# MCU_sheet.net
KiCad netlist of a schematic drawn in Altium Designer
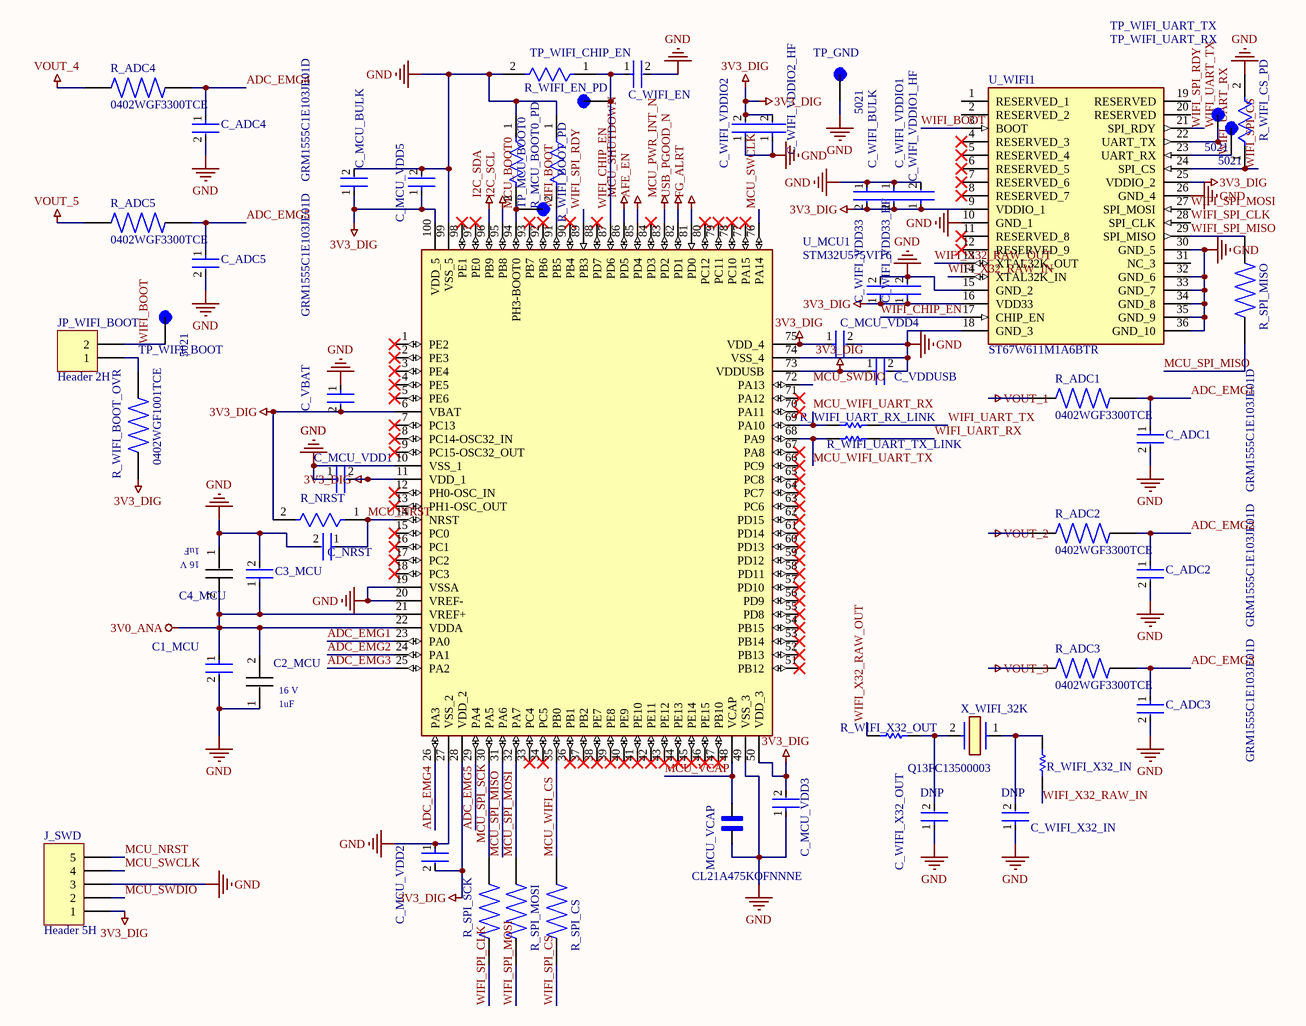
[diagram p0: MCU_sheet.SchDoc]

(export (version "E")
  (design (tool "Eeschema 10.0.6"))
  (components
    (comp (ref "C1_MCU")
      (value "GRM155R61C104KA88D")
      (footprint "96DF66F8-B997-472F-A885-42BCAAE661B2_FP-GRM155-0_05-IPC_C:FP-GRM155-0_05-IPC_C")
      (description "CAP CER 0.1UF 16V X5R 0402")
      (fields (field (name "VOLTAGE") "16V") (field (name "TOLERANCE") "10%"))
      (libsource (lib "EMG_Controlled_R5") (part "EMG_R5_C1_MCU"))
    )
    (comp (ref "C2_MCU")
      (value "MURATA_GRM155C71C105KE11D")
      (footprint "MURATA_GRM155C71C105KE11D_0:*MURATA_GRM155C71C105KE11D_0")
      (description "Murata GRM155C71C105KE11D: 1 uF 16 V X7S +/-10%, 0402/1005 metric")
      (fields (field (name "MF") "Murata") (field (name "MP") "GRM155C71C105KE11D"))
      (libsource (lib "EMG_Controlled_R5") (part "EMG_R5_C2_MCU"))
    )
    (comp (ref "C3_MCU")
      (value "GRM155R61C104KA88D")
      (footprint "96DF66F8-B997-472F-A885-42BCAAE661B2_FP-GRM155-0_05-IPC_C:FP-GRM155-0_05-IPC_C")
      (description "CAP CER 0.1UF 16V X5R 0402")
      (fields (field (name "VOLTAGE") "16V") (field (name "TOLERANCE") "10%"))
      (libsource (lib "EMG_Controlled_R5") (part "EMG_R5_C3_MCU"))
    )
    (comp (ref "C4_MCU")
      (value "MURATA_GRM155C71C105KE11D")
      (footprint "MURATA_GRM155C71C105KE11D_0:*MURATA_GRM155C71C105KE11D_0")
      (description "Murata GRM155C71C105KE11D: 1 uF 16 V X7S +/-10%, 0402/1005 metric")
      (fields (field (name "MF") "Murata") (field (name "MP") "GRM155C71C105KE11D"))
      (libsource (lib "EMG_Controlled_R5") (part "EMG_R5_C4_MCU"))
    )
    (comp (ref "C_ADC1")
      (value "GRM1555C1E103JE01D")
      (footprint "763A7EFC-D1AC-41FC-861F-90DBA274E34D_FP-GRM155-0_15-IPC_A:FP-GRM155-0_15-IPC_A")
      (description "Chip Multilayer Ceramic Capacitors for General Purpose, 0402, 10000pF, C0G, 30ppm/°C, 5%, 25V")
      (libsource (lib "EMG_Controlled_R5") (part "EMG_R5_C_ADC1"))
    )
    (comp (ref "C_ADC2")
      (value "GRM1555C1E103JE01D")
      (footprint "763A7EFC-D1AC-41FC-861F-90DBA274E34D_FP-GRM155-0_15-IPC_A:FP-GRM155-0_15-IPC_A")
      (description "Chip Multilayer Ceramic Capacitors for General Purpose, 0402, 10000pF, C0G, 30ppm/°C, 5%, 25V")
      (libsource (lib "EMG_Controlled_R5") (part "EMG_R5_C_ADC2"))
    )
    (comp (ref "C_ADC3")
      (value "GRM1555C1E103JE01D")
      (footprint "763A7EFC-D1AC-41FC-861F-90DBA274E34D_FP-GRM155-0_15-IPC_A:FP-GRM155-0_15-IPC_A")
      (description "Chip Multilayer Ceramic Capacitors for General Purpose, 0402, 10000pF, C0G, 30ppm/°C, 5%, 25V")
      (libsource (lib "EMG_Controlled_R5") (part "EMG_R5_C_ADC3"))
    )
    (comp (ref "C_ADC4")
      (value "GRM1555C1E103JE01D")
      (footprint "763A7EFC-D1AC-41FC-861F-90DBA274E34D_FP-GRM155-0_15-IPC_A:FP-GRM155-0_15-IPC_A")
      (description "Chip Multilayer Ceramic Capacitors for General Purpose, 0402, 10000pF, C0G, 30ppm/°C, 5%, 25V")
      (libsource (lib "EMG_Controlled_R5") (part "EMG_R5_C_ADC4"))
    )
    (comp (ref "C_ADC5")
      (value "GRM1555C1E103JE01D")
      (footprint "763A7EFC-D1AC-41FC-861F-90DBA274E34D_FP-GRM155-0_15-IPC_A:FP-GRM155-0_15-IPC_A")
      (description "Chip Multilayer Ceramic Capacitors for General Purpose, 0402, 10000pF, C0G, 30ppm/°C, 5%, 25V")
      (libsource (lib "EMG_Controlled_R5") (part "EMG_R5_C_ADC5"))
    )
    (comp (ref "C_MCU_BULK")
      (value "GCM21BC71E106KE36L")
      (footprint "936D640C-6583-4BC1-90EC-E059FB2B465D_FP-GCM21B-0_2-e0_2_0_7-MFG:FP-GCM21B-0_2-e0_2_0_7-MFG")
      (description "10 µF ±10% 25V Ceramic Capacitor X7S 0805 (2012 Metric)")
      (libsource (lib "EMG_Controlled_R5") (part "EMG_R5_C_MCU_BULK"))
    )
    (comp (ref "C_MCU_VDD1")
      (value "GRM155R61C104KA88D")
      (footprint "96DF66F8-B997-472F-A885-42BCAAE661B2_FP-GRM155-0_05-IPC_C:FP-GRM155-0_05-IPC_C")
      (description "CAP CER 0.1UF 16V X5R 0402")
      (fields (field (name "VOLTAGE") "16V") (field (name "TOLERANCE") "10%"))
      (libsource (lib "EMG_Controlled_R5") (part "EMG_R5_C_MCU_VDD1"))
    )
    (comp (ref "C_MCU_VDD2")
      (value "GRM155R61C104KA88D")
      (footprint "96DF66F8-B997-472F-A885-42BCAAE661B2_FP-GRM155-0_05-IPC_C:FP-GRM155-0_05-IPC_C")
      (description "CAP CER 0.1UF 16V X5R 0402")
      (fields (field (name "VOLTAGE") "16V") (field (name "TOLERANCE") "10%"))
      (libsource (lib "EMG_Controlled_R5") (part "EMG_R5_C_MCU_VDD2"))
    )
    (comp (ref "C_MCU_VDD3")
      (value "GRM155R61C104KA88D")
      (footprint "96DF66F8-B997-472F-A885-42BCAAE661B2_FP-GRM155-0_05-IPC_C:FP-GRM155-0_05-IPC_C")
      (description "CAP CER 0.1UF 16V X5R 0402")
      (fields (field (name "VOLTAGE") "16V") (field (name "TOLERANCE") "10%"))
      (libsource (lib "EMG_Controlled_R5") (part "EMG_R5_C_MCU_VDD3"))
    )
    (comp (ref "C_MCU_VDD4")
      (value "GRM155R61C104KA88D")
      (footprint "96DF66F8-B997-472F-A885-42BCAAE661B2_FP-GRM155-0_05-IPC_C:FP-GRM155-0_05-IPC_C")
      (description "CAP CER 0.1UF 16V X5R 0402")
      (fields (field (name "VOLTAGE") "16V") (field (name "TOLERANCE") "10%"))
      (libsource (lib "EMG_Controlled_R5") (part "EMG_R5_C_MCU_VDD4"))
    )
    (comp (ref "C_MCU_VDD5")
      (value "GRM155R61C104KA88D")
      (footprint "96DF66F8-B997-472F-A885-42BCAAE661B2_FP-GRM155-0_05-IPC_C:FP-GRM155-0_05-IPC_C")
      (description "CAP CER 0.1UF 16V X5R 0402")
      (fields (field (name "VOLTAGE") "16V") (field (name "TOLERANCE") "10%"))
      (libsource (lib "EMG_Controlled_R5") (part "EMG_R5_C_MCU_VDD5"))
    )
    (comp (ref "C_NRST")
      (value "GRM155R61C104KA88D")
      (footprint "96DF66F8-B997-472F-A885-42BCAAE661B2_FP-GRM155-0_05-IPC_C:FP-GRM155-0_05-IPC_C")
      (description "CAP CER 0.1UF 16V X5R 0402")
      (fields (field (name "VOLTAGE") "16V") (field (name "TOLERANCE") "10%"))
      (libsource (lib "EMG_Controlled_R5") (part "EMG_R5_C_NRST"))
    )
    (comp (ref "C_VBAT")
      (value "GRM155R61C104KA88D")
      (footprint "96DF66F8-B997-472F-A885-42BCAAE661B2_FP-GRM155-0_05-IPC_C:FP-GRM155-0_05-IPC_C")
      (description "CAP CER 0.1UF 16V X5R 0402")
      (fields (field (name "VOLTAGE") "16V") (field (name "TOLERANCE") "10%"))
      (libsource (lib "EMG_Controlled_R5") (part "EMG_R5_C_VBAT"))
    )
    (comp (ref "C_VDDUSB")
      (value "GRM155R61C104KA88D")
      (footprint "96DF66F8-B997-472F-A885-42BCAAE661B2_FP-GRM155-0_05-IPC_C:FP-GRM155-0_05-IPC_C")
      (description "CAP CER 0.1UF 16V X5R 0402")
      (fields (field (name "VOLTAGE") "16V") (field (name "TOLERANCE") "10%"))
      (libsource (lib "EMG_Controlled_R5") (part "EMG_R5_C_VDDUSB"))
    )
    (comp (ref "C_WIFI_BULK")
      (value "GRM219R60J476ME44D")
      (footprint "C53EA0CA-0507-449B-AA9E-0712004E71D5_FP-GRM219-0_2-0_1-IPC_A:FP-GRM219-0_2-0_1-IPC_A")
      (description "Chip Multilayer Ceramic Capacitors for General Purpose, 0805, 47uF, X5R, 15%, 20%, 6.3V")
      (fields (field (name "TOLERANCE") "20%"))
      (libsource (lib "EMG_Controlled_R5") (part "EMG_R5_C_WIFI_BULK"))
    )
    (comp (ref "C_WIFI_EN")
      (value "GRM155R61C104KA88D")
      (footprint "96DF66F8-B997-472F-A885-42BCAAE661B2_FP-GRM155-0_05-IPC_C:FP-GRM155-0_05-IPC_C")
      (description "CAP CER 0.1UF 16V X5R 0402")
      (fields (field (name "VOLTAGE") "16V") (field (name "TOLERANCE") "10%"))
      (libsource (lib "EMG_Controlled_R5") (part "EMG_R5_C_WIFI_EN"))
    )
    (comp (ref "C_WIFI_VDD33")
      (value "GCM21BC71E106KE36L")
      (footprint "936D640C-6583-4BC1-90EC-E059FB2B465D_FP-GCM21B-0_2-e0_2_0_7-MFG:FP-GCM21B-0_2-e0_2_0_7-MFG")
      (description "10 µF ±10% 25V Ceramic Capacitor X7S 0805 (2012 Metric)")
      (libsource (lib "EMG_Controlled_R5") (part "EMG_R5_C_WIFI_VDD33"))
    )
    (comp (ref "C_WIFI_VDD33_HF")
      (value "GRM155R61C104KA88D")
      (footprint "DB04E9CC-B2FF-43A3-BDC5-6EF387B10263_FP-GRM155-0_05-MFG:FP-GRM155-0_05-MFG")
      (description "CAP CER 0.1UF 16V X5R 0402")
      (fields (field (name "VOLTAGE") "16V") (field (name "TOLERANCE") "10%"))
      (libsource (lib "EMG_Controlled_R5") (part "EMG_R5_C_WIFI_VDD33_HF"))
    )
    (comp (ref "C_WIFI_VDDIO1")
      (value "GCM21BC71E106KE36L")
      (footprint "936D640C-6583-4BC1-90EC-E059FB2B465D_FP-GCM21B-0_2-e0_2_0_7-MFG:FP-GCM21B-0_2-e0_2_0_7-MFG")
      (description "10 µF ±10% 25V Ceramic Capacitor X7S 0805 (2012 Metric)")
      (libsource (lib "EMG_Controlled_R5") (part "EMG_R5_C_WIFI_VDDIO1"))
    )
    (comp (ref "C_WIFI_VDDIO1_HF")
      (value "GRM155R61C104KA88D")
      (footprint "DB04E9CC-B2FF-43A3-BDC5-6EF387B10263_FP-GRM155-0_05-MFG:FP-GRM155-0_05-MFG")
      (description "CAP CER 0.1UF 16V X5R 0402")
      (fields (field (name "VOLTAGE") "16V") (field (name "TOLERANCE") "10%"))
      (libsource (lib "EMG_Controlled_R5") (part "EMG_R5_C_WIFI_VDDIO1_HF"))
    )
    (comp (ref "C_WIFI_VDDIO2")
      (value "GCM21BC71E106KE36L")
      (footprint "936D640C-6583-4BC1-90EC-E059FB2B465D_FP-GCM21B-0_2-e0_2_0_7-MFG:FP-GCM21B-0_2-e0_2_0_7-MFG")
      (description "10 µF ±10% 25V Ceramic Capacitor X7S 0805 (2012 Metric)")
      (libsource (lib "EMG_Controlled_R5") (part "EMG_R5_C_WIFI_VDDIO2"))
    )
    (comp (ref "C_WIFI_VDDIO2_HF")
      (value "GRM155R61C104KA88D")
      (footprint "DB04E9CC-B2FF-43A3-BDC5-6EF387B10263_FP-GRM155-0_05-MFG:FP-GRM155-0_05-MFG")
      (description "CAP CER 0.1UF 16V X5R 0402")
      (fields (field (name "VOLTAGE") "16V") (field (name "TOLERANCE") "10%"))
      (libsource (lib "EMG_Controlled_R5") (part "EMG_R5_C_WIFI_VDDIO2_HF"))
    )
    (comp (ref "C_WIFI_X32_IN")
      (value "DNP")
      (footprint "96DF66F8-B997-472F-A885-42BCAAE661B2_FP-GRM155-0_05-IPC_C:FP-GRM155-0_05-IPC_C")
      (description "DNP - 32 kHz crystal tuning capacitor; no fitted value or MPN; retain 0402 footprint")
      (libsource (lib "EMG_Controlled_R5") (part "EMG_R5_C_WIFI_X32_IN"))
    )
    (comp (ref "C_WIFI_X32_OUT")
      (value "DNP")
      (footprint "96DF66F8-B997-472F-A885-42BCAAE661B2_FP-GRM155-0_05-IPC_C:FP-GRM155-0_05-IPC_C")
      (description "DNP - 32 kHz crystal tuning capacitor; no fitted value or MPN; retain 0402 footprint")
      (libsource (lib "EMG_Controlled_R5") (part "EMG_R5_C_WIFI_X32_OUT"))
    )
    (comp (ref "JP_WIFI_BOOT")
      (value "Header 2H")
      (footprint "Miscellaneous_Connectors_0:HDR1X2H")
      (description "Header, 2-Pin, Right Angle")
      (fields (field (name "PUBLISHER") "Altium Limited"))
      (libsource (lib "EMG_Controlled_R5") (part "EMG_R5_JP_WIFI_BOOT"))
    )
    (comp (ref "J_SWD")
      (value "Header 5H")
      (footprint "Miscellaneous_Connectors_0:HDR1X5H")
      (description "Header, 5-Pin, Right Angle")
      (fields (field (name "PUBLISHER") "Altium Limited"))
      (libsource (lib "EMG_Controlled_R5") (part "EMG_R5_J_SWD"))
    )
    (comp (ref "MCU_VCAP")
      (value "CL21A475KOFNNNE")
      (footprint "CL21A475KOFNNNE_0:CAPC2012X135N")
      (description "4.7 ÂµF Â±10% 16V Ceramic Capacitor X5R 0805 (2012 Metric)")
      (fields (field (name "MF") "Samsung"))
      (libsource (lib "EMG_Controlled_R5") (part "EMG_R5_MCU_VCAP"))
    )
    (comp (ref "R_ADC1")
      (value "0402WGF3300TCE")
      (footprint "0402WGF3300TCE_0:RESC1005X40N")
      (description "330 Ohm 1/16W Thick Film Resistor 0402 Chip - Surface Mount")
      (fields (field (name "MF") "Uni-Royal"))
      (libsource (lib "EMG_Controlled_R5") (part "EMG_R5_R_ADC1"))
    )
    (comp (ref "R_ADC2")
      (value "0402WGF3300TCE")
      (footprint "0402WGF3300TCE_0:RESC1005X40N")
      (description "330 Ohm 1/16W Thick Film Resistor 0402 Chip - Surface Mount")
      (fields (field (name "MF") "Uni-Royal"))
      (libsource (lib "EMG_Controlled_R5") (part "EMG_R5_R_ADC2"))
    )
    (comp (ref "R_ADC3")
      (value "0402WGF3300TCE")
      (footprint "0402WGF3300TCE_0:RESC1005X40N")
      (description "330 Ohm 1/16W Thick Film Resistor 0402 Chip - Surface Mount")
      (fields (field (name "MF") "Uni-Royal"))
      (libsource (lib "EMG_Controlled_R5") (part "EMG_R5_R_ADC3"))
    )
    (comp (ref "R_ADC4")
      (value "0402WGF3300TCE")
      (footprint "0402WGF3300TCE_0:RESC1005X40N")
      (description "330 Ohm 1/16W Thick Film Resistor 0402 Chip - Surface Mount")
      (fields (field (name "MF") "Uni-Royal"))
      (libsource (lib "EMG_Controlled_R5") (part "EMG_R5_R_ADC4"))
    )
    (comp (ref "R_ADC5")
      (value "0402WGF3300TCE")
      (footprint "0402WGF3300TCE_0:RESC1005X40N")
      (description "330 Ohm 1/16W Thick Film Resistor 0402 Chip - Surface Mount")
      (fields (field (name "MF") "Uni-Royal"))
      (libsource (lib "EMG_Controlled_R5") (part "EMG_R5_R_ADC5"))
    )
    (comp (ref "R_MCU_BOOT0_PD")
      (value "RT0402BRD0710KL")
      (footprint "B876F212-A29A-4983-9BB8-539D1BA2EBA1_FP-RT0402-MFG:FP-RT0402-MFG")
      (description "RES 10.0K OHM 1/16W .1% SMD 0402")
      (fields
        (field (name "MANUFACTURER") "Yageo")
        (field (name "OCTOPART") "https://octopart.com/rt0402brd0710kl-yageo-1181432")
      )
      (libsource (lib "EMG_Controlled_R5") (part "EMG_R5_R_MCU_BOOT0_PD"))
    )
    (comp (ref "R_NRST")
      (value "RT0402BRD0710KL")
      (footprint "B876F212-A29A-4983-9BB8-539D1BA2EBA1_FP-RT0402-MFG:FP-RT0402-MFG")
      (description "RES 10.0K OHM 1/16W .1% SMD 0402")
      (fields
        (field (name "MANUFACTURER") "Yageo")
        (field (name "OCTOPART") "https://octopart.com/rt0402brd0710kl-yageo-1181432")
      )
      (libsource (lib "EMG_Controlled_R5") (part "EMG_R5_R_NRST"))
    )
    (comp (ref "R_SPI_CS")
      (value "ERJ2RKF22R0X")
      (footprint "ERJ2RKF22R0X_0:RES_ERJ2RKF22R0X")
      (description "22 Ohms Â±1% 0.1W, 1/10W Chip Resistor 0402 (1005 Metric) Automotive AEC-Q200 Thick Film")
      (fields (field (name "MF") "Panasonic") (field (name "DIGI-KEY_PART_NUMBER") "P22.0LTR-ND"))
      (libsource (lib "EMG_Controlled_R5") (part "EMG_R5_R_SPI_CS"))
    )
    (comp (ref "R_SPI_MISO")
      (value "ERJ2RKF22R0X")
      (footprint "ERJ2RKF22R0X_0:RES_ERJ2RKF22R0X")
      (description "22 Ohms Â±1% 0.1W, 1/10W Chip Resistor 0402 (1005 Metric) Automotive AEC-Q200 Thick Film")
      (fields (field (name "MF") "Panasonic") (field (name "DIGI-KEY_PART_NUMBER") "P22.0LTR-ND"))
      (libsource (lib "EMG_Controlled_R5") (part "EMG_R5_R_SPI_MISO"))
    )
    (comp (ref "R_SPI_MOSI")
      (value "ERJ2RKF22R0X")
      (footprint "ERJ2RKF22R0X_0:RES_ERJ2RKF22R0X")
      (description "22 Ohms Â±1% 0.1W, 1/10W Chip Resistor 0402 (1005 Metric) Automotive AEC-Q200 Thick Film")
      (fields (field (name "MF") "Panasonic") (field (name "DIGI-KEY_PART_NUMBER") "P22.0LTR-ND"))
      (libsource (lib "EMG_Controlled_R5") (part "EMG_R5_R_SPI_MOSI"))
    )
    (comp (ref "R_SPI_SCK")
      (value "ERJ2RKF22R0X")
      (footprint "ERJ2RKF22R0X_0:RES_ERJ2RKF22R0X")
      (description "22 Ohms Â±1% 0.1W, 1/10W Chip Resistor 0402 (1005 Metric) Automotive AEC-Q200 Thick Film")
      (fields (field (name "MF") "Panasonic") (field (name "DIGI-KEY_PART_NUMBER") "P22.0LTR-ND"))
      (libsource (lib "EMG_Controlled_R5") (part "EMG_R5_R_SPI_SCK"))
    )
    (comp (ref "R_WIFI_BOOT_OVR")
      (value "0402WGF1001TCE")
      (footprint "0402WGF1001TCE_0:RESC1005X40N")
      (description "1K Ohm 1/16W Thick Film Resistor 0402 Chip - Surface Mount")
      (fields (field (name "MF") "Uni-Royal"))
      (libsource (lib "EMG_Controlled_R5") (part "EMG_R5_R_WIFI_BOOT_OVR"))
    )
    (comp (ref "R_WIFI_BOOT_PD")
      (value "RT0402BRD0710KL")
      (footprint "B876F212-A29A-4983-9BB8-539D1BA2EBA1_FP-RT0402-MFG:FP-RT0402-MFG")
      (description "RES 10.0K OHM 1/16W .1% SMD 0402")
      (fields
        (field (name "MANUFACTURER") "Yageo")
        (field (name "OCTOPART") "https://octopart.com/rt0402brd0710kl-yageo-1181432")
      )
      (libsource (lib "EMG_Controlled_R5") (part "EMG_R5_R_WIFI_BOOT_PD"))
    )
    (comp (ref "R_WIFI_CS_PD")
      (value "RT0402BRD0710KL")
      (footprint "B876F212-A29A-4983-9BB8-539D1BA2EBA1_FP-RT0402-MFG:FP-RT0402-MFG")
      (description "RES 10.0K OHM 1/16W .1% SMD 0402")
      (fields
        (field (name "MANUFACTURER") "Yageo")
        (field (name "OCTOPART") "https://octopart.com/rt0402brd0710kl-yageo-1181432")
      )
      (libsource (lib "EMG_Controlled_R5") (part "EMG_R5_R_WIFI_CS_PD"))
    )
    (comp (ref "R_WIFI_EN_PD")
      (value "RT0402BRD0710KL")
      (footprint "B876F212-A29A-4983-9BB8-539D1BA2EBA1_FP-RT0402-MFG:FP-RT0402-MFG")
      (description "RES 10.0K OHM 1/16W .1% SMD 0402")
      (fields
        (field (name "MANUFACTURER") "Yageo")
        (field (name "OCTOPART") "https://octopart.com/rt0402brd0710kl-yageo-1181432")
      )
      (libsource (lib "EMG_Controlled_R5") (part "EMG_R5_R_WIFI_EN_PD"))
    )
    (comp (ref "R_WIFI_UART_RX_LINK")
      (value "ERJ2GE0R00X")
      (footprint "9A3BC7AA-5BFE-4103-83F7-76F281EFC21D_RESC1005X40X25LL05T05:RESC1005X40X25LL05T05")
      (description "Chip Resistor, 0 Ohm, 0.1 W, -55 to 155 degC, 0402 (1005 Metric), RoHS, Tape and Reel")
      (fields (field (name "MANUFACTURER") "Panasonic") (field (name "TOLERANCE") "5%"))
      (libsource (lib "EMG_Controlled_R5") (part "EMG_R5_R_WIFI_UART_RX_LINK"))
    )
    (comp (ref "R_WIFI_UART_TX_LINK")
      (value "ERJ2GE0R00X")
      (footprint "9A3BC7AA-5BFE-4103-83F7-76F281EFC21D_RESC1005X40X25LL05T05:RESC1005X40X25LL05T05")
      (description "Chip Resistor, 0 Ohm, 0.1 W, -55 to 155 degC, 0402 (1005 Metric), RoHS, Tape and Reel")
      (fields (field (name "MANUFACTURER") "Panasonic") (field (name "TOLERANCE") "5%"))
      (libsource (lib "EMG_Controlled_R5") (part "EMG_R5_R_WIFI_UART_TX_LINK"))
    )
    (comp (ref "R_WIFI_X32_IN")
      (value "ERJ2GE0R00X")
      (footprint "9A3BC7AA-5BFE-4103-83F7-76F281EFC21D_RESC1005X40X25LL05T05:RESC1005X40X25LL05T05")
      (description "Chip Resistor, 0 Ohm, 0.1 W, -55 to 155 degC, 0402 (1005 Metric), RoHS, Tape and Reel")
      (fields (field (name "MANUFACTURER") "Panasonic") (field (name "TOLERANCE") "5%"))
      (libsource (lib "EMG_Controlled_R5") (part "EMG_R5_R_WIFI_X32_IN"))
    )
    (comp (ref "R_WIFI_X32_OUT")
      (value "ERJ2GE0R00X")
      (footprint "9A3BC7AA-5BFE-4103-83F7-76F281EFC21D_RESC1005X40X25LL05T05:RESC1005X40X25LL05T05")
      (description "Chip Resistor, 0 Ohm, 0.1 W, -55 to 155 degC, 0402 (1005 Metric), RoHS, Tape and Reel")
      (fields (field (name "MANUFACTURER") "Panasonic") (field (name "TOLERANCE") "5%"))
      (libsource (lib "EMG_Controlled_R5") (part "EMG_R5_R_WIFI_X32_OUT"))
    )
    (comp (ref "TP_GND")
      (value "5021")
      (footprint "5021_0:TP_5021")
      (description "UltraLow Profile THM Test Point-No Base")
      (fields (field (name "MF") "Keystone Electronics"))
      (libsource (lib "EMG_Controlled_R5") (part "EMG_R5_TP_GND"))
    )
    (comp (ref "TP_MCU_BOOT0")
      (value "5021")
      (footprint "5021_0:TP_5021")
      (description "UltraLow Profile THM Test Point-No Base")
      (fields (field (name "MF") "Keystone Electronics"))
      (libsource (lib "EMG_Controlled_R5") (part "EMG_R5_TP_MCU_BOOT0"))
    )
    (comp (ref "TP_WIFI_BOOT")
      (value "5021")
      (footprint "5021_0:TP_5021")
      (description "UltraLow Profile THM Test Point-No Base")
      (fields (field (name "MF") "Keystone Electronics"))
      (libsource (lib "EMG_Controlled_R5") (part "EMG_R5_TP_WIFI_BOOT"))
    )
    (comp (ref "TP_WIFI_CHIP_EN")
      (value "5021")
      (footprint "5021_0:TP_5021")
      (description "UltraLow Profile THM Test Point-No Base")
      (fields (field (name "MF") "Keystone Electronics"))
      (libsource (lib "EMG_Controlled_R5") (part "EMG_R5_TP_WIFI_CHIP_EN"))
    )
    (comp (ref "TP_WIFI_UART_RX")
      (value "5021")
      (footprint "5021_0:TP_5021")
      (description "UltraLow Profile THM Test Point-No Base")
      (fields (field (name "MF") "Keystone Electronics"))
      (libsource (lib "EMG_Controlled_R5") (part "EMG_R5_TP_WIFI_UART_RX"))
    )
    (comp (ref "TP_WIFI_UART_TX")
      (value "5021")
      (footprint "5021_0:TP_5021")
      (description "UltraLow Profile THM Test Point-No Base")
      (fields (field (name "MF") "Keystone Electronics"))
      (libsource (lib "EMG_Controlled_R5") (part "EMG_R5_TP_WIFI_UART_TX"))
    )
    (comp (ref "U_MCU1")
      (value "STM32U575VIT6")
      (footprint "SamacSys:QFP50P1600X1600X160-100N")
      (description "Integrated Circuit")
      (fields (field (name "MOUSER PART NUMBER") "511-STM32U575VIT6"))
      (libsource (lib "EMG_Controlled_R5") (part "EMG_R5_U_MCU1"))
    )
    (comp (ref "U_WIFI1")
      (value "ST67W611M1A6BTR")
      (footprint "SamacSys:ST67W611M1A6BTR")
      (description "Integrated Circuit")
      (libsource (lib "EMG_Controlled_R5") (part "EMG_R5_U_WIFI1"))
    )
    (comp (ref "X_WIFI_32K")
      (value "Q13FC13500003")
      (footprint "EMG_Crystal_R5:EMG_FC135_3215_2P")
      (description "Epson FC-135 32.768 kHz 9 pF +/-20 ppm, ESR 70 kohm max, 3.2x1.5 mm, 2 terminals")
      (fields
        (field (name "MANUFACTURER") "Seiko Epson Corporation")
        (field (name "TOLERANCE") "+/-20 ppm at 25 degC, 0.1 uW")
      )
      (libsource (lib "EMG_Controlled_R5") (part "EMG_R5_X_WIFI_32K"))
    )
  )
  (nets
    (net (code "1") (name "/ADC_EMG1") (class "Default")
      (node (ref "C_ADC1") (pin "1") (pinfunction "1_1") (pintype "passive"))
      (node (ref "R_ADC1") (pin "2") (pinfunction "2_2") (pintype "passive"))
      (node (ref "U_MCU1") (pin "23") (pinfunction "PA0_23") (pintype "bidirectional"))
    )
    (net (code "2") (name "/ADC_EMG2") (class "Default")
      (node (ref "C_ADC2") (pin "1") (pinfunction "1_1") (pintype "passive"))
      (node (ref "R_ADC2") (pin "2") (pinfunction "2_2") (pintype "passive"))
      (node (ref "U_MCU1") (pin "24") (pinfunction "PA1_24") (pintype "bidirectional"))
    )
    (net (code "3") (name "/ADC_EMG3") (class "Default")
      (node (ref "C_ADC3") (pin "1") (pinfunction "1_1") (pintype "passive"))
      (node (ref "R_ADC3") (pin "2") (pinfunction "2_2") (pintype "passive"))
      (node (ref "U_MCU1") (pin "25") (pinfunction "PA2_25") (pintype "bidirectional"))
    )
    (net (code "4") (name "/ADC_EMG4") (class "Default")
      (node (ref "C_ADC4") (pin "1") (pinfunction "1_1") (pintype "passive"))
      (node (ref "R_ADC4") (pin "2") (pinfunction "2_2") (pintype "passive"))
      (node (ref "U_MCU1") (pin "26") (pinfunction "PA3_26") (pintype "bidirectional"))
    )
    (net (code "5") (name "/ADC_EMG5") (class "Default")
      (node (ref "C_ADC5") (pin "1") (pinfunction "1_1") (pintype "passive"))
      (node (ref "R_ADC5") (pin "2") (pinfunction "2_2") (pintype "passive"))
      (node (ref "U_MCU1") (pin "29") (pinfunction "PA4_29") (pintype "bidirectional"))
    )
    (net (code "6") (name "/MCU_BOOT0") (class "Default")
      (node (ref "R_MCU_BOOT0_PD") (pin "2") (pinfunction "2_2") (pintype "passive"))
      (node (ref "TP_MCU_BOOT0") (pin "TP") (pinfunction "TP_TP") (pintype "passive"))
      (node (ref "U_MCU1") (pin "94") (pinfunction "PH3-BOOT0_94") (pintype "bidirectional"))
    )
    (net (code "7") (name "/MCU_NRST") (class "Default")
      (node (ref "C_NRST") (pin "1") (pinfunction "1_1") (pintype "passive"))
      (node (ref "J_SWD") (pin "5") (pinfunction "5_5") (pintype "passive"))
      (node (ref "R_NRST") (pin "1") (pinfunction "1_1") (pintype "passive"))
      (node (ref "U_MCU1") (pin "14") (pinfunction "NRST_14") (pintype "bidirectional"))
    )
    (net (code "8") (name "/MCU_SPI_MISO") (class "Default")
      (node (ref "R_SPI_MISO") (pin "2") (pinfunction "2_2") (pintype "passive"))
      (node (ref "U_MCU1") (pin "31") (pinfunction "PA6_31") (pintype "bidirectional"))
    )
    (net (code "9") (name "/MCU_SPI_MOSI") (class "Default")
      (node (ref "R_SPI_MOSI") (pin "2") (pinfunction "2_2") (pintype "passive"))
      (node (ref "U_MCU1") (pin "32") (pinfunction "PA7_32") (pintype "bidirectional"))
    )
    (net (code "10") (name "/MCU_SPI_SCK") (class "Default")
      (node (ref "R_SPI_SCK") (pin "2") (pinfunction "2_2") (pintype "passive"))
      (node (ref "U_MCU1") (pin "30") (pinfunction "PA5_30") (pintype "bidirectional"))
    )
    (net (code "11") (name "/MCU_SWCLK") (class "Default")
      (node (ref "J_SWD") (pin "4") (pinfunction "4_4") (pintype "passive"))
      (node (ref "U_MCU1") (pin "76") (pinfunction "PA14_76") (pintype "bidirectional"))
    )
    (net (code "12") (name "/MCU_SWDIO") (class "Default")
      (node (ref "J_SWD") (pin "2") (pinfunction "2_2") (pintype "passive"))
      (node (ref "U_MCU1") (pin "72") (pinfunction "PA13_72") (pintype "bidirectional"))
    )
    (net (code "13") (name "/MCU_VCAP") (class "Default")
      (node (ref "MCU_VCAP") (pin "2") (pinfunction "2_2") (pintype "passive"))
      (node (ref "U_MCU1") (pin "48") (pinfunction "VCAP_48") (pintype "power_in"))
    )
    (net (code "14") (name "/MCU_WIFI_CS") (class "Default")
      (node (ref "R_SPI_CS") (pin "2") (pinfunction "2_2") (pintype "passive"))
      (node (ref "U_MCU1") (pin "35") (pinfunction "PB0_35") (pintype "bidirectional"))
    )
    (net (code "15") (name "/MCU_WIFI_UART_RX") (class "Default")
      (node (ref "R_WIFI_UART_RX_LINK") (pin "2") (pinfunction "2_2") (pintype "passive"))
      (node (ref "U_MCU1") (pin "69") (pinfunction "PA10_69") (pintype "bidirectional"))
    )
    (net (code "16") (name "/MCU_WIFI_UART_TX") (class "Default")
      (node (ref "R_WIFI_UART_TX_LINK") (pin "2") (pinfunction "2_2") (pintype "passive"))
      (node (ref "U_MCU1") (pin "68") (pinfunction "PA9_68") (pintype "bidirectional"))
    )
    (net (code "17") (name "/WIFI_BOOT") (class "Default")
      (node (ref "JP_WIFI_BOOT") (pin "2") (pinfunction "2_2") (pintype "passive"))
      (node (ref "R_WIFI_BOOT_PD") (pin "2") (pinfunction "2_2") (pintype "passive"))
      (node (ref "TP_WIFI_BOOT") (pin "TP") (pinfunction "TP_TP") (pintype "passive"))
      (node (ref "U_MCU1") (pin "91") (pinfunction "PB5_91") (pintype "bidirectional"))
      (node (ref "U_WIFI1") (pin "3") (pinfunction "BOOT_3") (pintype "input"))
    )
    (net (code "18") (name "/WIFI_CHIP_EN") (class "Default")
      (node (ref "C_WIFI_EN") (pin "1") (pinfunction "1_1") (pintype "passive"))
      (node (ref "R_WIFI_EN_PD") (pin "1") (pinfunction "1_1") (pintype "passive"))
      (node (ref "TP_WIFI_CHIP_EN") (pin "TP") (pinfunction "TP_TP") (pintype "passive"))
      (node (ref "U_MCU1") (pin "87") (pinfunction "PD6_87") (pintype "bidirectional"))
      (node (ref "U_WIFI1") (pin "17") (pinfunction "CHIP_EN_17") (pintype "input"))
    )
    (net (code "19") (name "/WIFI_SPI_CLK") (class "Default")
      (node (ref "R_SPI_SCK") (pin "1") (pinfunction "1_1") (pintype "passive"))
      (node (ref "U_WIFI1") (pin "28") (pinfunction "SPI_CLK_28") (pintype "input"))
    )
    (net (code "20") (name "/WIFI_SPI_CS") (class "Default")
      (node (ref "R_SPI_CS") (pin "1") (pinfunction "1_1") (pintype "passive"))
      (node (ref "R_WIFI_CS_PD") (pin "1") (pinfunction "1_1") (pintype "passive"))
      (node (ref "U_WIFI1") (pin "24") (pinfunction "SPI_CS_24") (pintype "input"))
    )
    (net (code "21") (name "/WIFI_SPI_MISO") (class "Default")
      (node (ref "R_SPI_MISO") (pin "1") (pinfunction "1_1") (pintype "passive"))
      (node (ref "U_WIFI1") (pin "29") (pinfunction "SPI_MISO_29") (pintype "output"))
    )
    (net (code "22") (name "/WIFI_SPI_MOSI") (class "Default")
      (node (ref "R_SPI_MOSI") (pin "1") (pinfunction "1_1") (pintype "passive"))
      (node (ref "U_WIFI1") (pin "27") (pinfunction "SPI_MOSI_27") (pintype "input"))
    )
    (net (code "23") (name "/WIFI_SPI_RDY") (class "Default")
      (node (ref "U_MCU1") (pin "89") (pinfunction "PB3_89") (pintype "input"))
      (node (ref "U_WIFI1") (pin "21") (pinfunction "SPI_RDY_21") (pintype "output"))
    )
    (net (code "24") (name "/WIFI_UART_RX") (class "Default")
      (node (ref "R_WIFI_UART_TX_LINK") (pin "1") (pinfunction "1_1") (pintype "passive"))
      (node (ref "TP_WIFI_UART_RX") (pin "TP") (pinfunction "TP_TP") (pintype "passive"))
      (node (ref "U_WIFI1") (pin "23") (pinfunction "UART_RX_23") (pintype "input"))
    )
    (net (code "25") (name "/WIFI_UART_TX") (class "Default")
      (node (ref "R_WIFI_UART_RX_LINK") (pin "1") (pinfunction "1_1") (pintype "passive"))
      (node (ref "TP_WIFI_UART_TX") (pin "TP") (pinfunction "TP_TP") (pintype "passive"))
      (node (ref "U_WIFI1") (pin "22") (pinfunction "UART_TX_22") (pintype "output"))
    )
    (net (code "26") (name "/WIFI_X32_RAW_IN") (class "Default")
      (node (ref "R_WIFI_X32_IN") (pin "2") (pinfunction "2_2") (pintype "passive"))
      (node (ref "U_WIFI1") (pin "14") (pinfunction "XTAL32K_IN_14") (pintype "bidirectional"))
    )
    (net (code "27") (name "/WIFI_X32_RAW_OUT") (class "Default")
      (node (ref "R_WIFI_X32_OUT") (pin "2") (pinfunction "2_2") (pintype "passive"))
      (node (ref "U_WIFI1") (pin "13") (pinfunction "XTAL32K_OUT_13") (pintype "bidirectional"))
    )
    (net (code "28") (name "3V0_ANA") (class "Default")
      (node (ref "C1_MCU") (pin "1") (pinfunction "1_1") (pintype "passive"))
      (node (ref "C2_MCU") (pin "2") (pinfunction "2_2") (pintype "passive"))
      (node (ref "C3_MCU") (pin "1") (pinfunction "1_1") (pintype "passive"))
      (node (ref "C4_MCU") (pin "2") (pinfunction "2_2") (pintype "passive"))
      (node (ref "U_MCU1") (pin "21") (pinfunction "VREF+_21") (pintype "power_in"))
      (node (ref "U_MCU1") (pin "22") (pinfunction "VDDA_22") (pintype "power_in"))
    )
    (net (code "29") (name "3V3_DIG") (class "Default")
      (node (ref "C_MCU_BULK") (pin "1") (pinfunction "1_1") (pintype "passive"))
      (node (ref "C_MCU_VDD1") (pin "2") (pinfunction "2_2") (pintype "passive"))
      (node (ref "C_MCU_VDD2") (pin "2") (pinfunction "2_2") (pintype "passive"))
      (node (ref "C_MCU_VDD3") (pin "2") (pinfunction "2_2") (pintype "passive"))
      (node (ref "C_MCU_VDD4") (pin "1") (pinfunction "1_1") (pintype "passive"))
      (node (ref "C_MCU_VDD5") (pin "1") (pinfunction "1_1") (pintype "passive"))
      (node (ref "C_VBAT") (pin "2") (pinfunction "2_2") (pintype "passive"))
      (node (ref "C_VDDUSB") (pin "1") (pinfunction "1_1") (pintype "passive"))
      (node (ref "C_WIFI_BULK") (pin "2") (pinfunction "2_2") (pintype "passive"))
      (node (ref "C_WIFI_VDD33") (pin "1") (pinfunction "1_1") (pintype "passive"))
      (node (ref "C_WIFI_VDD33_HF") (pin "1") (pinfunction "1_1") (pintype "passive"))
      (node (ref "C_WIFI_VDDIO1") (pin "2") (pinfunction "2_2") (pintype "passive"))
      (node (ref "C_WIFI_VDDIO1_HF") (pin "1") (pinfunction "1_1") (pintype "passive"))
      (node (ref "C_WIFI_VDDIO2") (pin "2") (pinfunction "2_2") (pintype "passive"))
      (node (ref "C_WIFI_VDDIO2_HF") (pin "2") (pinfunction "2_2") (pintype "passive"))
      (node (ref "J_SWD") (pin "1") (pinfunction "1_1") (pintype "passive"))
      (node (ref "R_NRST") (pin "2") (pinfunction "2_2") (pintype "passive"))
      (node (ref "R_WIFI_BOOT_OVR") (pin "1") (pinfunction "1_1") (pintype "passive"))
      (node (ref "U_MCU1") (pin "100") (pinfunction "VDD_5_100") (pintype "power_in"))
      (node (ref "U_MCU1") (pin "11") (pinfunction "VDD_1_11") (pintype "power_in"))
      (node (ref "U_MCU1") (pin "28") (pinfunction "VDD_2_28") (pintype "power_in"))
      (node (ref "U_MCU1") (pin "50") (pinfunction "VDD_3_50") (pintype "power_in"))
      (node (ref "U_MCU1") (pin "6") (pinfunction "VBAT_6") (pintype "power_in"))
      (node (ref "U_MCU1") (pin "73") (pinfunction "VDDUSB_73") (pintype "power_in"))
      (node (ref "U_MCU1") (pin "75") (pinfunction "VDD_4_75") (pintype "power_in"))
      (node (ref "U_WIFI1") (pin "16") (pinfunction "VDD33_16") (pintype "power_in"))
      (node (ref "U_WIFI1") (pin "25") (pinfunction "VDDIO_2_25") (pintype "power_in"))
      (node (ref "U_WIFI1") (pin "9") (pinfunction "VDDIO_1_9") (pintype "power_in"))
    )
    (net (code "30") (name "AFE_EN") (class "Default")
      (node (ref "U_MCU1") (pin "85") (pinfunction "PD4_85") (pintype "bidirectional"))
    )
    (net (code "31") (name "FG_ALRT") (class "Default")
      (node (ref "U_MCU1") (pin "81") (pinfunction "PD0_81") (pintype "input"))
    )
    (net (code "32") (name "GND") (class "Default")
      (node (ref "C1_MCU") (pin "2") (pinfunction "2_2") (pintype "passive"))
      (node (ref "C2_MCU") (pin "1") (pinfunction "1_1") (pintype "passive"))
      (node (ref "C3_MCU") (pin "2") (pinfunction "2_2") (pintype "passive"))
      (node (ref "C4_MCU") (pin "1") (pinfunction "1_1") (pintype "passive"))
      (node (ref "C_ADC1") (pin "2") (pinfunction "2_2") (pintype "passive"))
      (node (ref "C_ADC2") (pin "2") (pinfunction "2_2") (pintype "passive"))
      (node (ref "C_ADC3") (pin "2") (pinfunction "2_2") (pintype "passive"))
      (node (ref "C_ADC4") (pin "2") (pinfunction "2_2") (pintype "passive"))
      (node (ref "C_ADC5") (pin "2") (pinfunction "2_2") (pintype "passive"))
      (node (ref "C_MCU_BULK") (pin "2") (pinfunction "2_2") (pintype "passive"))
      (node (ref "C_MCU_VDD1") (pin "1") (pinfunction "1_1") (pintype "passive"))
      (node (ref "C_MCU_VDD2") (pin "1") (pinfunction "1_1") (pintype "passive"))
      (node (ref "C_MCU_VDD3") (pin "1") (pinfunction "1_1") (pintype "passive"))
      (node (ref "C_MCU_VDD4") (pin "2") (pinfunction "2_2") (pintype "passive"))
      (node (ref "C_MCU_VDD5") (pin "2") (pinfunction "2_2") (pintype "passive"))
      (node (ref "C_NRST") (pin "2") (pinfunction "2_2") (pintype "passive"))
      (node (ref "C_VBAT") (pin "1") (pinfunction "1_1") (pintype "passive"))
      (node (ref "C_VDDUSB") (pin "2") (pinfunction "2_2") (pintype "passive"))
      (node (ref "C_WIFI_BULK") (pin "1") (pinfunction "1_1") (pintype "passive"))
      (node (ref "C_WIFI_EN") (pin "2") (pinfunction "2_2") (pintype "passive"))
      (node (ref "C_WIFI_VDD33") (pin "2") (pinfunction "2_2") (pintype "passive"))
      (node (ref "C_WIFI_VDD33_HF") (pin "2") (pinfunction "2_2") (pintype "passive"))
      (node (ref "C_WIFI_VDDIO1") (pin "1") (pinfunction "1_1") (pintype "passive"))
      (node (ref "C_WIFI_VDDIO1_HF") (pin "2") (pinfunction "2_2") (pintype "passive"))
      (node (ref "C_WIFI_VDDIO2") (pin "1") (pinfunction "1_1") (pintype "passive"))
      (node (ref "C_WIFI_VDDIO2_HF") (pin "1") (pinfunction "1_1") (pintype "passive"))
      (node (ref "C_WIFI_X32_IN") (pin "1") (pinfunction "1_1") (pintype "passive"))
      (node (ref "C_WIFI_X32_OUT") (pin "1") (pinfunction "1_1") (pintype "passive"))
      (node (ref "J_SWD") (pin "3") (pinfunction "3_3") (pintype "passive"))
      (node (ref "MCU_VCAP") (pin "1") (pinfunction "1_1") (pintype "passive"))
      (node (ref "R_MCU_BOOT0_PD") (pin "1") (pinfunction "1_1") (pintype "passive"))
      (node (ref "R_WIFI_BOOT_PD") (pin "1") (pinfunction "1_1") (pintype "passive"))
      (node (ref "R_WIFI_CS_PD") (pin "2") (pinfunction "2_2") (pintype "passive"))
      (node (ref "R_WIFI_EN_PD") (pin "2") (pinfunction "2_2") (pintype "passive"))
      (node (ref "TP_GND") (pin "TP") (pinfunction "TP_TP") (pintype "passive"))
      (node (ref "U_MCU1") (pin "10") (pinfunction "VSS_1_10") (pintype "power_in"))
      (node (ref "U_MCU1") (pin "19") (pinfunction "VSSA_19") (pintype "power_in"))
      (node (ref "U_MCU1") (pin "20") (pinfunction "VREF-_20") (pintype "power_in"))
      (node (ref "U_MCU1") (pin "27") (pinfunction "VSS_2_27") (pintype "power_in"))
      (node (ref "U_MCU1") (pin "49") (pinfunction "VSS_3_49") (pintype "power_in"))
      (node (ref "U_MCU1") (pin "74") (pinfunction "VSS_4_74") (pintype "power_in"))
      (node (ref "U_MCU1") (pin "99") (pinfunction "VSS_5_99") (pintype "power_in"))
      (node (ref "U_WIFI1") (pin "10") (pinfunction "GND_1_10") (pintype "power_in"))
      (node (ref "U_WIFI1") (pin "15") (pinfunction "GND_2_15") (pintype "power_in"))
      (node (ref "U_WIFI1") (pin "18") (pinfunction "GND_3_18") (pintype "power_in"))
      (node (ref "U_WIFI1") (pin "26") (pinfunction "GND_4_26") (pintype "power_in"))
      (node (ref "U_WIFI1") (pin "30") (pinfunction "GND_5_30") (pintype "power_in"))
      (node (ref "U_WIFI1") (pin "32") (pinfunction "GND_6_32") (pintype "power_in"))
      (node (ref "U_WIFI1") (pin "33") (pinfunction "GND_7_33") (pintype "power_in"))
      (node (ref "U_WIFI1") (pin "34") (pinfunction "GND_8_34") (pintype "power_in"))
      (node (ref "U_WIFI1") (pin "35") (pinfunction "GND_9_35") (pintype "power_in"))
      (node (ref "U_WIFI1") (pin "36") (pinfunction "GND_10_36") (pintype "power_in"))
    )
    (net (code "33") (name "I2C_SCL") (class "Default")
      (node (ref "U_MCU1") (pin "95") (pinfunction "PB8_95") (pintype "bidirectional"))
    )
    (net (code "34") (name "I2C_SDA") (class "Default")
      (node (ref "U_MCU1") (pin "96") (pinfunction "PB9_96") (pintype "bidirectional"))
    )
    (net (code "35") (name "MCU_PWR_INT_N") (class "Default")
      (node (ref "U_MCU1") (pin "83") (pinfunction "PD2_83") (pintype "bidirectional"))
    )
    (net (code "36") (name "MCU_SHUTDOWN") (class "Default")
      (node (ref "U_MCU1") (pin "86") (pinfunction "PD5_86") (pintype "bidirectional"))
    )
    (net (code "37") (name "Net-(JP_WIFI_BOOT-Pad1)") (class "Default")
      (node (ref "JP_WIFI_BOOT") (pin "1") (pinfunction "1_1") (pintype "passive"))
      (node (ref "R_WIFI_BOOT_OVR") (pin "2") (pinfunction "2_2") (pintype "passive"))
    )
    (net (code "38") (name "Net-(X_WIFI_32K-CRYSTAL_1)") (class "Default")
      (node (ref "C_WIFI_X32_IN") (pin "2") (pinfunction "2_2") (pintype "passive"))
      (node (ref "R_WIFI_X32_IN") (pin "1") (pinfunction "1_1") (pintype "passive"))
      (node (ref "X_WIFI_32K") (pin "1") (pinfunction "CRYSTAL_1_1") (pintype "passive"))
    )
    (net (code "39") (name "Net-(X_WIFI_32K-CRYSTAL_2)") (class "Default")
      (node (ref "C_WIFI_X32_OUT") (pin "2") (pinfunction "2_2") (pintype "passive"))
      (node (ref "R_WIFI_X32_OUT") (pin "1") (pinfunction "1_1") (pintype "passive"))
      (node (ref "X_WIFI_32K") (pin "2") (pinfunction "CRYSTAL_2_2") (pintype "passive"))
    )
    (net (code "40") (name "USB_PGOOD_N") (class "Default")
      (node (ref "U_MCU1") (pin "82") (pinfunction "PD1_82") (pintype "bidirectional"))
    )
    (net (code "41") (name "VOUT_1") (class "Default")
      (node (ref "R_ADC1") (pin "1") (pinfunction "1_1") (pintype "passive"))
    )
    (net (code "42") (name "VOUT_2") (class "Default")
      (node (ref "R_ADC2") (pin "1") (pinfunction "1_1") (pintype "passive"))
    )
    (net (code "43") (name "VOUT_3") (class "Default")
      (node (ref "R_ADC3") (pin "1") (pinfunction "1_1") (pintype "passive"))
    )
    (net (code "44") (name "VOUT_4") (class "Default")
      (node (ref "R_ADC4") (pin "1") (pinfunction "1_1") (pintype "passive"))
    )
    (net (code "45") (name "VOUT_5") (class "Default")
      (node (ref "R_ADC5") (pin "1") (pinfunction "1_1") (pintype "passive"))
    )
    (net (code "46") (name "unconnected-(U_MCU1-PA8-Pad67)") (class "Default")
      (node (ref "U_MCU1") (pin "67") (pinfunction "PA8_67") (pintype "bidirectional+no_connect"))
    )
    (net (code "47") (name "unconnected-(U_MCU1-PA11-Pad70)") (class "Default")
      (node (ref "U_MCU1") (pin "70") (pinfunction "PA11_70") (pintype "bidirectional+no_connect"))
    )
    (net (code "48") (name "unconnected-(U_MCU1-PA12-Pad71)") (class "Default")
      (node (ref "U_MCU1") (pin "71") (pinfunction "PA12_71") (pintype "bidirectional+no_connect"))
    )
    (net (code "49") (name "unconnected-(U_MCU1-PA15-Pad77)") (class "Default")
      (node (ref "U_MCU1") (pin "77") (pinfunction "PA15_77") (pintype "bidirectional+no_connect"))
    )
    (net (code "50") (name "unconnected-(U_MCU1-PB1-Pad36)") (class "Default")
      (node (ref "U_MCU1") (pin "36") (pinfunction "PB1_36") (pintype "bidirectional+no_connect"))
    )
    (net (code "51") (name "unconnected-(U_MCU1-PB2-Pad37)") (class "Default")
      (node (ref "U_MCU1") (pin "37") (pinfunction "PB2_37") (pintype "bidirectional+no_connect"))
    )
    (net (code "52") (name "unconnected-(U_MCU1-PB4-Pad90)") (class "Default")
      (node (ref "U_MCU1") (pin "90") (pinfunction "PB4_90") (pintype "bidirectional+no_connect"))
    )
    (net (code "53") (name "unconnected-(U_MCU1-PB6-Pad92)") (class "Default")
      (node (ref "U_MCU1") (pin "92") (pinfunction "PB6_92") (pintype "bidirectional+no_connect"))
    )
    (net (code "54") (name "unconnected-(U_MCU1-PB7-Pad93)") (class "Default")
      (node (ref "U_MCU1") (pin "93") (pinfunction "PB7_93") (pintype "bidirectional+no_connect"))
    )
    (net (code "55") (name "unconnected-(U_MCU1-PB10-Pad47)") (class "Default")
      (node (ref "U_MCU1") (pin "47") (pinfunction "PB10_47") (pintype "bidirectional+no_connect"))
    )
    (net (code "56") (name "unconnected-(U_MCU1-PB12-Pad51)") (class "Default")
      (node (ref "U_MCU1") (pin "51") (pinfunction "PB12_51") (pintype "bidirectional+no_connect"))
    )
    (net (code "57") (name "unconnected-(U_MCU1-PB13-Pad52)") (class "Default")
      (node (ref "U_MCU1") (pin "52") (pinfunction "PB13_52") (pintype "bidirectional+no_connect"))
    )
    (net (code "58") (name "unconnected-(U_MCU1-PB14-Pad53)") (class "Default")
      (node (ref "U_MCU1") (pin "53") (pinfunction "PB14_53") (pintype "bidirectional+no_connect"))
    )
    (net (code "59") (name "unconnected-(U_MCU1-PB15-Pad54)") (class "Default")
      (node (ref "U_MCU1") (pin "54") (pinfunction "PB15_54") (pintype "bidirectional+no_connect"))
    )
    (net (code "60") (name "unconnected-(U_MCU1-PC0-Pad15)") (class "Default")
      (node (ref "U_MCU1") (pin "15") (pinfunction "PC0_15") (pintype "bidirectional+no_connect"))
    )
    (net (code "61") (name "unconnected-(U_MCU1-PC1-Pad16)") (class "Default")
      (node (ref "U_MCU1") (pin "16") (pinfunction "PC1_16") (pintype "bidirectional+no_connect"))
    )
    (net (code "62") (name "unconnected-(U_MCU1-PC2-Pad17)") (class "Default")
      (node (ref "U_MCU1") (pin "17") (pinfunction "PC2_17") (pintype "bidirectional+no_connect"))
    )
    (net (code "63") (name "unconnected-(U_MCU1-PC3-Pad18)") (class "Default")
      (node (ref "U_MCU1") (pin "18") (pinfunction "PC3_18") (pintype "bidirectional+no_connect"))
    )
    (net (code "64") (name "unconnected-(U_MCU1-PC4-Pad33)") (class "Default")
      (node (ref "U_MCU1") (pin "33") (pinfunction "PC4_33") (pintype "bidirectional+no_connect"))
    )
    (net (code "65") (name "unconnected-(U_MCU1-PC5-Pad34)") (class "Default")
      (node (ref "U_MCU1") (pin "34") (pinfunction "PC5_34") (pintype "bidirectional+no_connect"))
    )
    (net (code "66") (name "unconnected-(U_MCU1-PC6-Pad63)") (class "Default")
      (node (ref "U_MCU1") (pin "63") (pinfunction "PC6_63") (pintype "bidirectional+no_connect"))
    )
    (net (code "67") (name "unconnected-(U_MCU1-PC7-Pad64)") (class "Default")
      (node (ref "U_MCU1") (pin "64") (pinfunction "PC7_64") (pintype "bidirectional+no_connect"))
    )
    (net (code "68") (name "unconnected-(U_MCU1-PC8-Pad65)") (class "Default")
      (node (ref "U_MCU1") (pin "65") (pinfunction "PC8_65") (pintype "bidirectional+no_connect"))
    )
    (net (code "69") (name "unconnected-(U_MCU1-PC9-Pad66)") (class "Default")
      (node (ref "U_MCU1") (pin "66") (pinfunction "PC9_66") (pintype "bidirectional+no_connect"))
    )
    (net (code "70") (name "unconnected-(U_MCU1-PC10-Pad78)") (class "Default")
      (node (ref "U_MCU1") (pin "78") (pinfunction "PC10_78") (pintype "bidirectional+no_connect"))
    )
    (net (code "71") (name "unconnected-(U_MCU1-PC11-Pad79)") (class "Default")
      (node (ref "U_MCU1") (pin "79") (pinfunction "PC11_79") (pintype "bidirectional+no_connect"))
    )
    (net (code "72") (name "unconnected-(U_MCU1-PC12-Pad80)") (class "Default")
      (node (ref "U_MCU1") (pin "80") (pinfunction "PC12_80") (pintype "bidirectional+no_connect"))
    )
    (net (code "73") (name "unconnected-(U_MCU1-PC13-Pad7)") (class "Default")
      (node (ref "U_MCU1") (pin "7") (pinfunction "PC13_7") (pintype "bidirectional+no_connect"))
    )
    (net (code "74") (name "unconnected-(U_MCU1-PC14-OSC32_IN-Pad8)") (class "Default")
      (node (ref "U_MCU1") (pin "8") (pinfunction "PC14-OSC32_IN_8") (pintype "bidirectional+no_connect"))
    )
    (net (code "75") (name "unconnected-(U_MCU1-PC15-OSC32_OUT-Pad9)") (class "Default")
      (node (ref "U_MCU1") (pin "9") (pinfunction "PC15-OSC32_OUT_9") (pintype "bidirectional+no_connect"))
    )
    (net (code "76") (name "unconnected-(U_MCU1-PD3-Pad84)") (class "Default")
      (node (ref "U_MCU1") (pin "84") (pinfunction "PD3_84") (pintype "bidirectional+no_connect"))
    )
    (net (code "77") (name "unconnected-(U_MCU1-PD7-Pad88)") (class "Default")
      (node (ref "U_MCU1") (pin "88") (pinfunction "PD7_88") (pintype "bidirectional+no_connect"))
    )
    (net (code "78") (name "unconnected-(U_MCU1-PD8-Pad55)") (class "Default")
      (node (ref "U_MCU1") (pin "55") (pinfunction "PD8_55") (pintype "bidirectional+no_connect"))
    )
    (net (code "79") (name "unconnected-(U_MCU1-PD9-Pad56)") (class "Default")
      (node (ref "U_MCU1") (pin "56") (pinfunction "PD9_56") (pintype "bidirectional+no_connect"))
    )
    (net (code "80") (name "unconnected-(U_MCU1-PD10-Pad57)") (class "Default")
      (node (ref "U_MCU1") (pin "57") (pinfunction "PD10_57") (pintype "bidirectional+no_connect"))
    )
    (net (code "81") (name "unconnected-(U_MCU1-PD11-Pad58)") (class "Default")
      (node (ref "U_MCU1") (pin "58") (pinfunction "PD11_58") (pintype "bidirectional+no_connect"))
    )
    (net (code "82") (name "unconnected-(U_MCU1-PD12-Pad59)") (class "Default")
      (node (ref "U_MCU1") (pin "59") (pinfunction "PD12_59") (pintype "bidirectional+no_connect"))
    )
    (net (code "83") (name "unconnected-(U_MCU1-PD13-Pad60)") (class "Default")
      (node (ref "U_MCU1") (pin "60") (pinfunction "PD13_60") (pintype "bidirectional+no_connect"))
    )
    (net (code "84") (name "unconnected-(U_MCU1-PD14-Pad61)") (class "Default")
      (node (ref "U_MCU1") (pin "61") (pinfunction "PD14_61") (pintype "bidirectional+no_connect"))
    )
    (net (code "85") (name "unconnected-(U_MCU1-PD15-Pad62)") (class "Default")
      (node (ref "U_MCU1") (pin "62") (pinfunction "PD15_62") (pintype "bidirectional+no_connect"))
    )
    (net (code "86") (name "unconnected-(U_MCU1-PE0-Pad97)") (class "Default")
      (node (ref "U_MCU1") (pin "97") (pinfunction "PE0_97") (pintype "bidirectional+no_connect"))
    )
    (net (code "87") (name "unconnected-(U_MCU1-PE1-Pad98)") (class "Default")
      (node (ref "U_MCU1") (pin "98") (pinfunction "PE1_98") (pintype "bidirectional+no_connect"))
    )
    (net (code "88") (name "unconnected-(U_MCU1-PE2-Pad1)") (class "Default")
      (node (ref "U_MCU1") (pin "1") (pinfunction "PE2_1") (pintype "bidirectional+no_connect"))
    )
    (net (code "89") (name "unconnected-(U_MCU1-PE3-Pad2)") (class "Default")
      (node (ref "U_MCU1") (pin "2") (pinfunction "PE3_2") (pintype "bidirectional+no_connect"))
    )
    (net (code "90") (name "unconnected-(U_MCU1-PE4-Pad3)") (class "Default")
      (node (ref "U_MCU1") (pin "3") (pinfunction "PE4_3") (pintype "bidirectional+no_connect"))
    )
    (net (code "91") (name "unconnected-(U_MCU1-PE5-Pad4)") (class "Default")
      (node (ref "U_MCU1") (pin "4") (pinfunction "PE5_4") (pintype "bidirectional+no_connect"))
    )
    (net (code "92") (name "unconnected-(U_MCU1-PE6-Pad5)") (class "Default")
      (node (ref "U_MCU1") (pin "5") (pinfunction "PE6_5") (pintype "bidirectional+no_connect"))
    )
    (net (code "93") (name "unconnected-(U_MCU1-PE7-Pad38)") (class "Default")
      (node (ref "U_MCU1") (pin "38") (pinfunction "PE7_38") (pintype "bidirectional+no_connect"))
    )
    (net (code "94") (name "unconnected-(U_MCU1-PE8-Pad39)") (class "Default")
      (node (ref "U_MCU1") (pin "39") (pinfunction "PE8_39") (pintype "bidirectional+no_connect"))
    )
    (net (code "95") (name "unconnected-(U_MCU1-PE9-Pad40)") (class "Default")
      (node (ref "U_MCU1") (pin "40") (pinfunction "PE9_40") (pintype "bidirectional+no_connect"))
    )
    (net (code "96") (name "unconnected-(U_MCU1-PE10-Pad41)") (class "Default")
      (node (ref "U_MCU1") (pin "41") (pinfunction "PE10_41") (pintype "bidirectional+no_connect"))
    )
    (net (code "97") (name "unconnected-(U_MCU1-PE11-Pad42)") (class "Default")
      (node (ref "U_MCU1") (pin "42") (pinfunction "PE11_42") (pintype "bidirectional+no_connect"))
    )
    (net (code "98") (name "unconnected-(U_MCU1-PE12-Pad43)") (class "Default")
      (node (ref "U_MCU1") (pin "43") (pinfunction "PE12_43") (pintype "bidirectional+no_connect"))
    )
    (net (code "99") (name "unconnected-(U_MCU1-PE13-Pad44)") (class "Default")
      (node (ref "U_MCU1") (pin "44") (pinfunction "PE13_44") (pintype "bidirectional+no_connect"))
    )
    (net (code "100") (name "unconnected-(U_MCU1-PE14-Pad45)") (class "Default")
      (node (ref "U_MCU1") (pin "45") (pinfunction "PE14_45") (pintype "bidirectional+no_connect"))
    )
    (net (code "101") (name "unconnected-(U_MCU1-PE15-Pad46)") (class "Default")
      (node (ref "U_MCU1") (pin "46") (pinfunction "PE15_46") (pintype "bidirectional+no_connect"))
    )
    (net (code "102") (name "unconnected-(U_MCU1-PH0-OSC_IN-Pad12)") (class "Default")
      (node (ref "U_MCU1") (pin "12") (pinfunction "PH0-OSC_IN_12") (pintype "bidirectional+no_connect"))
    )
    (net (code "103") (name "unconnected-(U_MCU1-PH1-OSC_OUT-Pad13)") (class "Default")
      (node (ref "U_MCU1") (pin "13") (pinfunction "PH1-OSC_OUT_13") (pintype "bidirectional+no_connect"))
    )
    (net (code "104") (name "unconnected-(U_WIFI1-NC_3-Pad31)") (class "Default")
      (node (ref "U_WIFI1") (pin "31") (pinfunction "NC_3_31") (pintype "passive"))
    )
    (net (code "105") (name "unconnected-(U_WIFI1-RESERVED-Pad19)") (class "Default")
      (node (ref "U_WIFI1") (pin "19") (pinfunction "RESERVED_19") (pintype "passive"))
    )
    (net (code "106") (name "unconnected-(U_WIFI1-RESERVED-Pad20)") (class "Default")
      (node (ref "U_WIFI1") (pin "20") (pinfunction "RESERVED_20") (pintype "passive"))
    )
    (net (code "107") (name "unconnected-(U_WIFI1-RESERVED_1-Pad1)") (class "Default")
      (node (ref "U_WIFI1") (pin "1") (pinfunction "RESERVED_1_1") (pintype "passive"))
    )
    (net (code "108") (name "unconnected-(U_WIFI1-RESERVED_2-Pad2)") (class "Default")
      (node (ref "U_WIFI1") (pin "2") (pinfunction "RESERVED_2_2") (pintype "passive"))
    )
    (net (code "109") (name "unconnected-(U_WIFI1-RESERVED_3-Pad4)") (class "Default")
      (node (ref "U_WIFI1") (pin "4") (pinfunction "RESERVED_3_4") (pintype "passive+no_connect"))
    )
    (net (code "110") (name "unconnected-(U_WIFI1-RESERVED_4-Pad5)") (class "Default")
      (node (ref "U_WIFI1") (pin "5") (pinfunction "RESERVED_4_5") (pintype "passive+no_connect"))
    )
    (net (code "111") (name "unconnected-(U_WIFI1-RESERVED_5-Pad6)") (class "Default")
      (node (ref "U_WIFI1") (pin "6") (pinfunction "RESERVED_5_6") (pintype "passive+no_connect"))
    )
    (net (code "112") (name "unconnected-(U_WIFI1-RESERVED_6-Pad7)") (class "Default")
      (node (ref "U_WIFI1") (pin "7") (pinfunction "RESERVED_6_7") (pintype "passive+no_connect"))
    )
    (net (code "113") (name "unconnected-(U_WIFI1-RESERVED_7-Pad8)") (class "Default")
      (node (ref "U_WIFI1") (pin "8") (pinfunction "RESERVED_7_8") (pintype "passive+no_connect"))
    )
    (net (code "114") (name "unconnected-(U_WIFI1-RESERVED_8-Pad11)") (class "Default")
      (node (ref "U_WIFI1") (pin "11") (pinfunction "RESERVED_8_11") (pintype "passive+no_connect"))
    )
    (net (code "115") (name "unconnected-(U_WIFI1-RESERVED_9-Pad12)") (class "Default")
      (node (ref "U_WIFI1") (pin "12") (pinfunction "RESERVED_9_12") (pintype "passive+no_connect"))
    )
  )
)
